# mcu.net
KiCad netlist of a schematic drawn in EAGLE
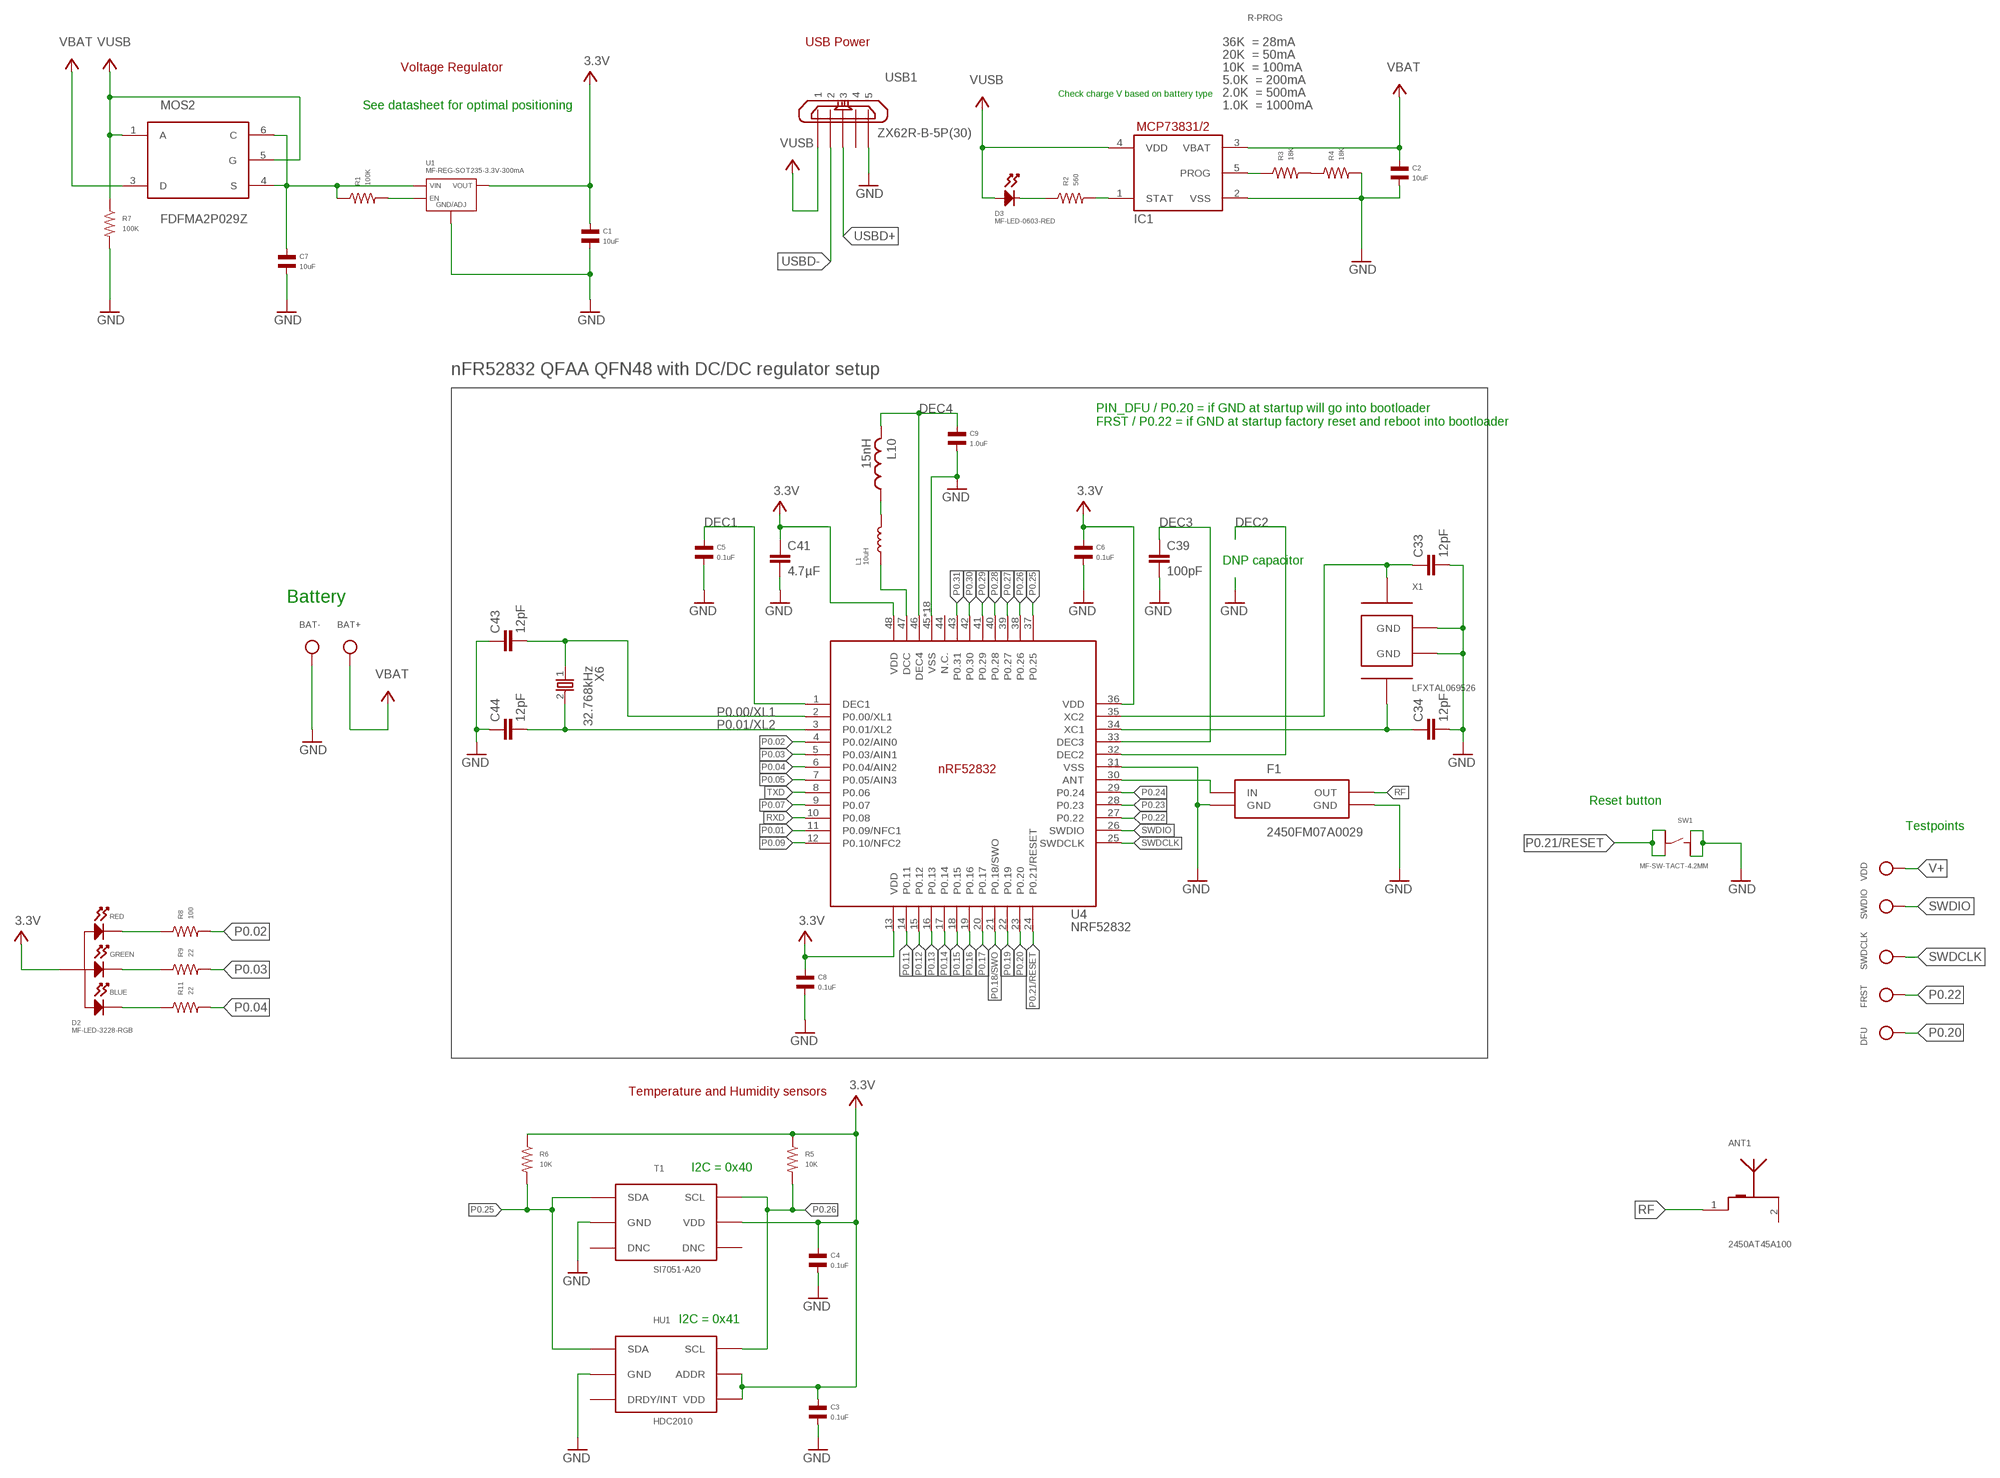
[diagram p0: schematic, sheet 1]

(export (version "E")
  (design (tool "Eeschema 10.0.6"))
  (components
    (comp (ref "ANT1")
      (value "2450AT45A100")
      (footprint "eagle-import:2450AT45A100")
      (fields (field (name "MPN") "2450AT45A100E"))
      (libsource (lib "eagle-import") (part "2450AT45A100"))
    )
    (comp (ref "BAT+")
      (value "TESTPOINTROUND2MM")
      (footprint "eagle-import:TESTPOINT_ROUND_2MM")
      (libsource (lib "eagle-import") (part "TESTPOINTROUND2MM"))
    )
    (comp (ref "BAT-")
      (value "TESTPOINTROUND2MM")
      (footprint "eagle-import:TESTPOINT_ROUND_2MM")
      (libsource (lib "eagle-import") (part "TESTPOINTROUND2MM"))
    )
    (comp (ref "C1")
      (value "10uF")
      (footprint "eagle-import:C0603")
      (fields (field (name "HOUSEPART") "YES") (field (name "MPN") "JMK107ABJ106KA-T"))
      (libsource (lib "eagle-import") (part "CAPACITOR_NP_0603"))
    )
    (comp (ref "C2")
      (value "10uF")
      (footprint "eagle-import:C0603")
      (fields (field (name "HOUSEPART") "YES") (field (name "MPN") "JMK107ABJ106KA-T"))
      (libsource (lib "eagle-import") (part "CAPACITOR_NP_0603"))
    )
    (comp (ref "C3")
      (value "0.1uF")
      (footprint "eagle-import:C0402")
      (fields (field (name "HOUSEPART") "YES") (field (name "MPN") "MF-CAP-0402-0.1uF"))
      (libsource (lib "eagle-import") (part "CAPACITOR_NP_0402"))
    )
    (comp (ref "C4")
      (value "0.1uF")
      (footprint "eagle-import:C0402")
      (fields (field (name "HOUSEPART") "YES") (field (name "MPN") "MF-CAP-0402-0.1uF"))
      (libsource (lib "eagle-import") (part "CAPACITOR_NP_0402"))
    )
    (comp (ref "C5")
      (value "0.1uF")
      (footprint "eagle-import:C0402")
      (fields (field (name "HOUSEPART") "YES") (field (name "MPN") "MF-CAP-0402-0.1uF"))
      (libsource (lib "eagle-import") (part "CAPACITOR_NP_0402"))
    )
    (comp (ref "C6")
      (value "0.1uF")
      (footprint "eagle-import:C0402")
      (fields (field (name "HOUSEPART") "YES") (field (name "MPN") "MF-CAP-0402-0.1uF"))
      (libsource (lib "eagle-import") (part "CAPACITOR_NP_0402"))
    )
    (comp (ref "C7")
      (value "10uF")
      (footprint "eagle-import:C0603")
      (fields (field (name "HOUSEPART") "YES") (field (name "MPN") "JMK107ABJ106KA-T"))
      (libsource (lib "eagle-import") (part "CAPACITOR_NP_0603"))
    )
    (comp (ref "C8")
      (value "0.1uF")
      (footprint "eagle-import:C0402")
      (fields (field (name "HOUSEPART") "YES") (field (name "MPN") "MF-CAP-0402-0.1uF"))
      (libsource (lib "eagle-import") (part "CAPACITOR_NP_0402"))
    )
    (comp (ref "C9")
      (value "1.0uF")
      (footprint "eagle-import:C0603")
      (fields (field (name "HOUSEPART") "YES") (field (name "MPN") "MF-CAP-0603-1uF"))
      (libsource (lib "eagle-import") (part "CAPACITOR_NP_0603"))
    )
    (comp (ref "C33")
      (value "12pF")
      (footprint "eagle-import:RESC0402_N")
      (fields (field (name "MPN") "C0402C120J5GACTU"))
      (libsource (lib "eagle-import") (part "CAPACITOR_0402_N"))
    )
    (comp (ref "C34")
      (value "12pF")
      (footprint "eagle-import:RESC0402_N")
      (fields (field (name "MPN") "C0402C120J5GACTU"))
      (libsource (lib "eagle-import") (part "CAPACITOR_0402_N"))
    )
    (comp (ref "C39")
      (value "100pF")
      (footprint "eagle-import:RESC0402_N")
      (fields (field (name "MPN") "GRM1555C1H101GA01D"))
      (libsource (lib "eagle-import") (part "CAPACITOR_0402_N"))
    )
    (comp (ref "C41")
      (value "4.7µF")
      (footprint "eagle-import:RESC0603_N")
      (fields (field (name "MPN") "06036D475KAT2A"))
      (libsource (lib "eagle-import") (part "CAPACITOR_0603_N"))
    )
    (comp (ref "C43")
      (value "12pF")
      (footprint "eagle-import:RESC0402_N")
      (fields (field (name "MPN") "C0402C120J5GACTU"))
      (libsource (lib "eagle-import") (part "CAPACITOR_0402_N"))
    )
    (comp (ref "C44")
      (value "12pF")
      (footprint "eagle-import:RESC0402_N")
      (fields (field (name "MPN") "C0402C120J5GACTU"))
      (libsource (lib "eagle-import") (part "CAPACITOR_0402_N"))
    )
    (comp (ref "D2")
      (value "MF-LED-3228-RGB")
      (footprint "eagle-import:PLCC4")
      (fields (field (name "HOUSEPART") "YES"))
      (libsource (lib "eagle-import") (part "LED_RGB_CA_PLCC4"))
    )
    (comp (ref "D3")
      (value "MF-LED-0603-RED")
      (footprint "eagle-import:LED0603")
      (fields (field (name "HOUSEPART") "YES"))
      (libsource (lib "eagle-import") (part "LED_SINGLE-0603-RED"))
    )
    (comp (ref "DFU")
      (value "TESTPOINTROUND2MM")
      (footprint "eagle-import:TESTPOINT_ROUND_2MM")
      (libsource (lib "eagle-import") (part "TESTPOINTROUND2MM"))
    )
    (comp (ref "F1")
      (value "2450FM07A0029")
      (footprint "eagle-import:0402_RF")
      (fields (field (name "MPN") "2450FM07A0029T"))
      (libsource (lib "eagle-import") (part "2450FM07A0029"))
    )
    (comp (ref "FRST")
      (value "TESTPOINTROUND2MM")
      (footprint "eagle-import:TESTPOINT_ROUND_2MM")
      (libsource (lib "eagle-import") (part "TESTPOINTROUND2MM"))
    )
    (comp (ref "HU1")
      (value "HDC2010")
      (footprint "eagle-import:DSBGA-6")
      (fields (field (name "MPN") "HDC2010YPAR"))
      (libsource (lib "eagle-import") (part "HDC2010"))
    )
    (comp (ref "IC1")
      (value "MCP73831/OT")
      (footprint "eagle-import:SOT23-5L")
      (fields (field (name "MPN") "MCP73831T-2ACI/OT"))
      (libsource (lib "eagle-import") (part "MCP73831/OT"))
    )
    (comp (ref "L1")
      (value "10uH")
      (footprint "eagle-import:L1210")
      (fields (field (name "HOUSEPART") "YES") (field (name "MPN") "MF-IND-1210-10uH"))
      (libsource (lib "eagle-import") (part "INDUCTOR_1210"))
    )
    (comp (ref "L10")
      (value "15nH")
      (footprint "eagle-import:RESC0402_N")
      (fields (field (name "MPN") "L-07C15NJV6T"))
      (libsource (lib "eagle-import") (part "INDUCTOR_0402_N"))
    )
    (comp (ref "MOS2")
      (value "FDFMA2P029Z")
      (footprint "eagle-import:MICROFET_2X2")
      (libsource (lib "eagle-import") (part "FDFMA2P029Z"))
    )
    (comp (ref "R1")
      (value "100K")
      (footprint "eagle-import:R0402")
      (fields (field (name "HOUSEPART") "YES") (field (name "MPN") "MF-RES-0402-100K"))
      (libsource (lib "eagle-import") (part "RESISTOR_0402"))
    )
    (comp (ref "R2")
      (value "560")
      (footprint "eagle-import:R0402")
      (fields (field (name "HOUSEPART") "YES") (field (name "MPN") "MF-RES-0402-560"))
      (libsource (lib "eagle-import") (part "RESISTOR_0402"))
    )
    (comp (ref "R3")
      (value "18K")
      (footprint "eagle-import:R0402")
      (fields (field (name "HOUSEPART") "YES") (field (name "MPN") "MF-RES-0402-18K"))
      (libsource (lib "eagle-import") (part "RESISTOR_0402"))
    )
    (comp (ref "R4")
      (value "18K")
      (footprint "eagle-import:R0402")
      (fields (field (name "HOUSEPART") "YES") (field (name "MPN") "MF-RES-0402-18K"))
      (libsource (lib "eagle-import") (part "RESISTOR_0402"))
    )
    (comp (ref "R5")
      (value "10K")
      (footprint "eagle-import:R0402")
      (fields (field (name "HOUSEPART") "YES") (field (name "MPN") "MF-RES-0402-10K"))
      (libsource (lib "eagle-import") (part "RESISTOR_0402"))
    )
    (comp (ref "R6")
      (value "10K")
      (footprint "eagle-import:R0402")
      (fields (field (name "HOUSEPART") "YES") (field (name "MPN") "MF-RES-0402-10K"))
      (libsource (lib "eagle-import") (part "RESISTOR_0402"))
    )
    (comp (ref "R7")
      (value "100K")
      (footprint "eagle-import:R0402")
      (fields (field (name "HOUSEPART") "YES") (field (name "MPN") "MF-RES-0402-100K"))
      (libsource (lib "eagle-import") (part "RESISTOR_0402"))
    )
    (comp (ref "R8")
      (value "100")
      (footprint "eagle-import:R0402")
      (fields (field (name "HOUSEPART") "YES") (field (name "MPN") "MF-RES-0402-100"))
      (libsource (lib "eagle-import") (part "RESISTOR_0402"))
    )
    (comp (ref "R9")
      (value "22")
      (footprint "eagle-import:R0402")
      (fields (field (name "HOUSEPART") "YES") (field (name "MPN") "MF-RES-0402-22"))
      (libsource (lib "eagle-import") (part "RESISTOR_0402"))
    )
    (comp (ref "R11")
      (value "22")
      (footprint "eagle-import:R0402")
      (fields (field (name "HOUSEPART") "YES") (field (name "MPN") "MF-RES-0402-22"))
      (libsource (lib "eagle-import") (part "RESISTOR_0402"))
    )
    (comp (ref "SW1")
      (value "MF-SW-TACT-4.2MM")
      (footprint "eagle-import:TACT4.2MM")
      (fields (field (name "HOUSEPART") "YES"))
      (libsource (lib "eagle-import") (part "TACT_4.2MM"))
    )
    (comp (ref "SWDCLK")
      (value "TESTPOINTROUND2MM")
      (footprint "eagle-import:TESTPOINT_ROUND_2MM")
      (libsource (lib "eagle-import") (part "TESTPOINTROUND2MM"))
    )
    (comp (ref "SWDIO")
      (value "TESTPOINTROUND2MM")
      (footprint "eagle-import:TESTPOINT_ROUND_2MM")
      (libsource (lib "eagle-import") (part "TESTPOINTROUND2MM"))
    )
    (comp (ref "T1")
      (value "SI7051-A20")
      (footprint "eagle-import:DFN-6")
      (fields (field (name "MPN") "SI7051-A20-IM"))
      (libsource (lib "eagle-import") (part "SI7051-A20"))
    )
    (comp (ref "U1")
      (value "MF-REG-SOT235-3.3V-300mA")
      (footprint "eagle-import:SOT-23-5")
      (fields (field (name "HOUSEPART") "YES"))
      (libsource (lib "eagle-import") (part "TLV70233PDBVR"))
    )
    (comp (ref "U4")
      (value "NRF52832")
      (footprint "eagle-import:QFN40P600X600X90-48_N")
      (fields (field (name "MPN") "NRF52832-QFAA-R7"))
      (libsource (lib "eagle-import") (part "NRF52832"))
    )
    (comp (ref "USB1")
      (value "ZX62R-B-5P(30)")
      (footprint "eagle-import:ZX62R-B-5P(30)")
      (libsource (lib "eagle-import") (part "ZX62R-B-5P(30)"))
    )
    (comp (ref "VDD")
      (value "TESTPOINTROUND2MM")
      (footprint "eagle-import:TESTPOINT_ROUND_2MM")
      (libsource (lib "eagle-import") (part "TESTPOINTROUND2MM"))
    )
    (comp (ref "X1")
      (value "LFXTAL069526")
      (footprint "eagle-import:1612")
      (fields (field (name "MPN") "LFXTAL069526CUTT"))
      (libsource (lib "eagle-import") (part "LFXTAL069526"))
    )
    (comp (ref "X6")
      (value "32.768kHz")
      (footprint "eagle-import:XTAL_3215_N")
      (fields (field (name "MPN") "LFXTAL009706REEL"))
      (libsource (lib "eagle-import") (part "XTAL_32KHZ"))
    )
  )
  (nets
    (net (code "1") (name "/DEC1") (class "Default")
      (node (ref "C5") (pin "P$1") (pinfunction "P$1_P$1") (pintype "passive"))
      (node (ref "U4") (pin "1") (pinfunction "DEC1_1") (pintype "power_in"))
    )
    (net (code "2") (name "/DEC2") (class "Default")
      (node (ref "U4") (pin "32") (pinfunction "DEC2_32") (pintype "bidirectional"))
    )
    (net (code "3") (name "/DEC3") (class "Default")
      (node (ref "C39") (pin "1") (pinfunction "1_1") (pintype "passive"))
      (node (ref "U4") (pin "33") (pinfunction "DEC3_33") (pintype "bidirectional"))
    )
    (net (code "4") (name "/DEC4") (class "Default")
      (node (ref "C9") (pin "P$1") (pinfunction "P$1_P$1") (pintype "passive"))
      (node (ref "L10") (pin "2") (pinfunction "2_2") (pintype "passive"))
      (node (ref "U4") (pin "46") (pinfunction "DEC4_46") (pintype "power_in"))
    )
    (net (code "5") (name "/P0.00{slash}XL1") (class "Default")
      (node (ref "C43") (pin "2") (pinfunction "2_2") (pintype "passive"))
      (node (ref "U4") (pin "2") (pinfunction "P0.00/XL1_2") (pintype "bidirectional"))
      (node (ref "X6") (pin "1") (pinfunction "1_1") (pintype "passive"))
    )
    (net (code "6") (name "/P0.01{slash}XL2") (class "Default")
      (node (ref "C44") (pin "2") (pinfunction "2_2") (pintype "passive"))
      (node (ref "U4") (pin "3") (pinfunction "P0.01/XL2_3") (pintype "bidirectional"))
      (node (ref "X6") (pin "2") (pinfunction "2_2") (pintype "passive"))
    )
    (net (code "7") (name "GND") (class "Default")
      (node (ref "BAT-") (pin "P$1") (pinfunction "P$1_P$1") (pintype "bidirectional"))
      (node (ref "C1") (pin "P$2") (pinfunction "P$2_P$2") (pintype "passive"))
      (node (ref "C2") (pin "P$2") (pinfunction "P$2_P$2") (pintype "passive"))
      (node (ref "C3") (pin "P$2") (pinfunction "P$2_P$2") (pintype "passive"))
      (node (ref "C33") (pin "2") (pinfunction "2_2") (pintype "passive"))
      (node (ref "C34") (pin "2") (pinfunction "2_2") (pintype "passive"))
      (node (ref "C39") (pin "2") (pinfunction "2_2") (pintype "passive"))
      (node (ref "C4") (pin "P$2") (pinfunction "P$2_P$2") (pintype "passive"))
      (node (ref "C41") (pin "2") (pinfunction "2_2") (pintype "passive"))
      (node (ref "C43") (pin "1") (pinfunction "1_1") (pintype "passive"))
      (node (ref "C44") (pin "1") (pinfunction "1_1") (pintype "passive"))
      (node (ref "C5") (pin "P$2") (pinfunction "P$2_P$2") (pintype "passive"))
      (node (ref "C6") (pin "P$2") (pinfunction "P$2_P$2") (pintype "passive"))
      (node (ref "C7") (pin "P$2") (pinfunction "P$2_P$2") (pintype "passive"))
      (node (ref "C8") (pin "P$2") (pinfunction "P$2_P$2") (pintype "passive"))
      (node (ref "C9") (pin "P$2") (pinfunction "P$2_P$2") (pintype "passive"))
      (node (ref "F1") (pin "GND@2") (pinfunction "GND_GND@2") (pintype "power_in"))
      (node (ref "F1") (pin "GND@4") (pinfunction "GND_GND@4") (pintype "power_in"))
      (node (ref "HU1") (pin "C1") (pinfunction "GND_C1") (pintype "power_in"))
      (node (ref "IC1") (pin "2") (pinfunction "VSS_2") (pintype "power_in"))
      (node (ref "R4") (pin "P$2") (pinfunction "P$2_P$2") (pintype "passive"))
      (node (ref "R7") (pin "P$2") (pinfunction "P$2_P$2") (pintype "passive"))
      (node (ref "SW1") (pin "P$1") (pinfunction "P$1_P$1") (pintype "bidirectional"))
      (node (ref "SW1") (pin "P$2") (pinfunction "P$2_P$2") (pintype "bidirectional"))
      (node (ref "T1") (pin "2") (pinfunction "GND_2") (pintype "power_in"))
      (node (ref "U1") (pin "P$2") (pinfunction "GND/ADJ_P$2") (pintype "bidirectional"))
      (node (ref "U4") (pin "31") (pinfunction "VSS_31") (pintype "bidirectional"))
      (node (ref "U4") (pin "45") (pinfunction "VSS_45") (pintype "power_in"))
      (node (ref "U4") (pin "PAD") (pinfunction "VSS_PAD") (pintype "power_in"))
      (node (ref "U4") (pin "PAD@VIA01") (pinfunction "VSS_PAD@VIA01") (pintype "power_in"))
      (node (ref "U4") (pin "PAD@VIA02") (pinfunction "VSS_PAD@VIA02") (pintype "power_in"))
      (node (ref "U4") (pin "PAD@VIA03") (pinfunction "VSS_PAD@VIA03") (pintype "power_in"))
      (node (ref "U4") (pin "PAD@VIA04") (pinfunction "VSS_PAD@VIA04") (pintype "power_in"))
      (node (ref "U4") (pin "PAD@VIA05") (pinfunction "VSS_PAD@VIA05") (pintype "power_in"))
      (node (ref "U4") (pin "PAD@VIA06") (pinfunction "VSS_PAD@VIA06") (pintype "power_in"))
      (node (ref "U4") (pin "PAD@VIA07") (pinfunction "VSS_PAD@VIA07") (pintype "power_in"))
      (node (ref "U4") (pin "PAD@VIA08") (pinfunction "VSS_PAD@VIA08") (pintype "power_in"))
      (node (ref "U4") (pin "PAD@VIA09") (pinfunction "VSS_PAD@VIA09") (pintype "power_in"))
      (node (ref "U4") (pin "PAD@VIA10") (pinfunction "VSS_PAD@VIA10") (pintype "power_in"))
      (node (ref "U4") (pin "PAD@VIA11") (pinfunction "VSS_PAD@VIA11") (pintype "power_in"))
      (node (ref "U4") (pin "PAD@VIA12") (pinfunction "VSS_PAD@VIA12") (pintype "power_in"))
      (node (ref "U4") (pin "PAD@VIA13") (pinfunction "VSS_PAD@VIA13") (pintype "power_in"))
      (node (ref "U4") (pin "PAD@VIA14") (pinfunction "VSS_PAD@VIA14") (pintype "power_in"))
      (node (ref "U4") (pin "PAD@VIA15") (pinfunction "VSS_PAD@VIA15") (pintype "power_in"))
      (node (ref "U4") (pin "PAD@VIA16") (pinfunction "VSS_PAD@VIA16") (pintype "power_in"))
      (node (ref "USB1") (pin "5") (pinfunction "5_5") (pintype "passive"))
      (node (ref "X1") (pin "2") (pinfunction "GND_2") (pintype "power_in"))
      (node (ref "X1") (pin "4") (pinfunction "GND_4") (pintype "power_in"))
    )
    (net (code "8") (name "Net-(D2-CATHODE_BLUE)") (class "Default")
      (node (ref "D2") (pin "P$4") (pinfunction "CATHODE_BLUE_P$4") (pintype "power_in"))
      (node (ref "R11") (pin "P$1") (pinfunction "P$1_P$1") (pintype "passive"))
    )
    (net (code "9") (name "Net-(D2-CATHODE_GREEN)") (class "Default")
      (node (ref "D2") (pin "P$3") (pinfunction "CATHODE_GREEN_P$3") (pintype "power_in"))
      (node (ref "R9") (pin "P$1") (pinfunction "P$1_P$1") (pintype "passive"))
    )
    (net (code "10") (name "Net-(D2-CATHODE_RED)") (class "Default")
      (node (ref "D2") (pin "P$2") (pinfunction "CATHODE_RED_P$2") (pintype "power_in"))
      (node (ref "R8") (pin "P$1") (pinfunction "P$1_P$1") (pintype "passive"))
    )
    (net (code "11") (name "Net-(D3-PadCATHODE)") (class "Default")
      (node (ref "D3") (pin "CATHODE") (pinfunction "CATHODE_CATHODE") (pintype "power_in"))
      (node (ref "R2") (pin "P$1") (pinfunction "P$1_P$1") (pintype "passive"))
    )
    (net (code "12") (name "Net-(F1-IN)") (class "Default")
      (node (ref "F1") (pin "1") (pinfunction "IN_1") (pintype "input"))
      (node (ref "U4") (pin "30") (pinfunction "ANT_30") (pintype "bidirectional"))
    )
    (net (code "13") (name "Net-(IC1-PROG)") (class "Default")
      (node (ref "IC1") (pin "5") (pinfunction "PROG_5") (pintype "input"))
      (node (ref "R3") (pin "P$1") (pinfunction "P$1_P$1") (pintype "passive"))
    )
    (net (code "14") (name "Net-(IC1-STAT)") (class "Default")
      (node (ref "IC1") (pin "1") (pinfunction "STAT_1") (pintype "output"))
      (node (ref "R2") (pin "P$2") (pinfunction "P$2_P$2") (pintype "passive"))
    )
    (net (code "15") (name "Net-(L1-PadP$2)") (class "Default")
      (node (ref "L1") (pin "P$2") (pinfunction "P$2_P$2") (pintype "passive"))
      (node (ref "L10") (pin "1") (pinfunction "1_1") (pintype "passive"))
    )
    (net (code "16") (name "Net-(MOS2-C)") (class "Default")
      (node (ref "C7") (pin "P$1") (pinfunction "P$1_P$1") (pintype "passive"))
      (node (ref "MOS2") (pin "4") (pinfunction "S_4") (pintype "bidirectional"))
      (node (ref "MOS2") (pin "6") (pinfunction "C_6") (pintype "bidirectional"))
      (node (ref "R1") (pin "P$1") (pinfunction "P$1_P$1") (pintype "passive"))
      (node (ref "U1") (pin "P$1") (pinfunction "VIN_P$1") (pintype "bidirectional"))
    )
    (net (code "17") (name "Net-(R3-PadP$2)") (class "Default")
      (node (ref "R3") (pin "P$2") (pinfunction "P$2_P$2") (pintype "passive"))
      (node (ref "R4") (pin "P$1") (pinfunction "P$1_P$1") (pintype "passive"))
    )
    (net (code "18") (name "Net-(U1-EN)") (class "Default")
      (node (ref "R1") (pin "P$2") (pinfunction "P$2_P$2") (pintype "passive"))
      (node (ref "U1") (pin "P$3") (pinfunction "EN_P$3") (pintype "bidirectional"))
    )
    (net (code "19") (name "Net-(U4-DCC)") (class "Default")
      (node (ref "L1") (pin "P$1") (pinfunction "P$1_P$1") (pintype "passive"))
      (node (ref "U4") (pin "47") (pinfunction "DCC_47") (pintype "output"))
    )
    (net (code "20") (name "Net-(U4-XC1)") (class "Default")
      (node (ref "C34") (pin "1") (pinfunction "1_1") (pintype "passive"))
      (node (ref "U4") (pin "34") (pinfunction "XC1_34") (pintype "input"))
      (node (ref "X1") (pin "1") (pinfunction "1_1") (pintype "bidirectional"))
    )
    (net (code "21") (name "Net-(U4-XC2)") (class "Default")
      (node (ref "C33") (pin "1") (pinfunction "1_1") (pintype "passive"))
      (node (ref "U4") (pin "35") (pinfunction "XC2_35") (pintype "output"))
      (node (ref "X1") (pin "3") (pinfunction "2_3") (pintype "bidirectional"))
    )
    (net (code "22") (name "P0.01") (class "Default")
      (node (ref "U4") (pin "11") (pinfunction "P0.09/NFC1_11") (pintype "bidirectional"))
    )
    (net (code "23") (name "P0.02") (class "Default")
      (node (ref "R8") (pin "P$2") (pinfunction "P$2_P$2") (pintype "passive"))
      (node (ref "U4") (pin "4") (pinfunction "P0.02/AIN0_4") (pintype "bidirectional"))
    )
    (net (code "24") (name "P0.03") (class "Default")
      (node (ref "R9") (pin "P$2") (pinfunction "P$2_P$2") (pintype "passive"))
      (node (ref "U4") (pin "5") (pinfunction "P0.03/AIN1_5") (pintype "bidirectional"))
    )
    (net (code "25") (name "P0.04") (class "Default")
      (node (ref "R11") (pin "P$2") (pinfunction "P$2_P$2") (pintype "passive"))
      (node (ref "U4") (pin "6") (pinfunction "P0.04/AIN2_6") (pintype "bidirectional"))
    )
    (net (code "26") (name "P0.05") (class "Default")
      (node (ref "U4") (pin "7") (pinfunction "P0.05/AIN3_7") (pintype "bidirectional"))
    )
    (net (code "27") (name "P0.07") (class "Default")
      (node (ref "U4") (pin "9") (pinfunction "P0.07_9") (pintype "bidirectional"))
    )
    (net (code "28") (name "P0.09") (class "Default")
      (node (ref "U4") (pin "12") (pinfunction "P0.10/NFC2_12") (pintype "bidirectional"))
    )
    (net (code "29") (name "P0.11") (class "Default")
      (node (ref "U4") (pin "14") (pinfunction "P0.11_14") (pintype "bidirectional"))
    )
    (net (code "30") (name "P0.12") (class "Default")
      (node (ref "U4") (pin "15") (pinfunction "P0.12_15") (pintype "bidirectional"))
    )
    (net (code "31") (name "P0.13") (class "Default")
      (node (ref "U4") (pin "16") (pinfunction "P0.13_16") (pintype "bidirectional"))
    )
    (net (code "32") (name "P0.14") (class "Default")
      (node (ref "U4") (pin "17") (pinfunction "P0.14_17") (pintype "bidirectional"))
    )
    (net (code "33") (name "P0.15") (class "Default")
      (node (ref "U4") (pin "18") (pinfunction "P0.15_18") (pintype "bidirectional"))
    )
    (net (code "34") (name "P0.16") (class "Default")
      (node (ref "U4") (pin "19") (pinfunction "P0.16_19") (pintype "bidirectional"))
    )
    (net (code "35") (name "P0.17") (class "Default")
      (node (ref "U4") (pin "20") (pinfunction "P0.17_20") (pintype "bidirectional"))
    )
    (net (code "36") (name "P0.18{slash}SWO") (class "Default")
      (node (ref "U4") (pin "21") (pinfunction "P0.18/SWO_21") (pintype "bidirectional"))
    )
    (net (code "37") (name "P0.19") (class "Default")
      (node (ref "U4") (pin "22") (pinfunction "P0.19_22") (pintype "bidirectional"))
    )
    (net (code "38") (name "P0.20") (class "Default")
      (node (ref "DFU") (pin "P$1") (pinfunction "P$1_P$1") (pintype "bidirectional"))
      (node (ref "U4") (pin "23") (pinfunction "P0.20_23") (pintype "bidirectional"))
    )
    (net (code "39") (name "P0.21{slash}RESET") (class "Default")
      (node (ref "SW1") (pin "P$3") (pinfunction "P$3_P$3") (pintype "bidirectional"))
      (node (ref "SW1") (pin "P$4") (pinfunction "P$4_P$4") (pintype "bidirectional"))
      (node (ref "U4") (pin "24") (pinfunction "P0.21/RESET_24") (pintype "bidirectional"))
    )
    (net (code "40") (name "P0.22") (class "Default")
      (node (ref "FRST") (pin "P$1") (pinfunction "P$1_P$1") (pintype "bidirectional"))
      (node (ref "U4") (pin "27") (pinfunction "P0.22_27") (pintype "bidirectional"))
    )
    (net (code "41") (name "P0.23") (class "Default")
      (node (ref "U4") (pin "28") (pinfunction "P0.23_28") (pintype "bidirectional"))
    )
    (net (code "42") (name "P0.24") (class "Default")
      (node (ref "U4") (pin "29") (pinfunction "P0.24_29") (pintype "bidirectional"))
    )
    (net (code "43") (name "P0.25") (class "Default")
      (node (ref "HU1") (pin "A2") (pinfunction "SDA_A2") (pintype "bidirectional"))
      (node (ref "R6") (pin "P$2") (pinfunction "P$2_P$2") (pintype "passive"))
      (node (ref "T1") (pin "1") (pinfunction "SDA_1") (pintype "bidirectional"))
      (node (ref "U4") (pin "37") (pinfunction "P0.25_37") (pintype "bidirectional"))
    )
    (net (code "44") (name "P0.26") (class "Default")
      (node (ref "HU1") (pin "B2") (pinfunction "SCL_B2") (pintype "input"))
      (node (ref "R5") (pin "P$2") (pinfunction "P$2_P$2") (pintype "passive"))
      (node (ref "T1") (pin "6") (pinfunction "SCL_6") (pintype "bidirectional"))
      (node (ref "U4") (pin "38") (pinfunction "P0.26_38") (pintype "bidirectional"))
    )
    (net (code "45") (name "P0.27") (class "Default")
      (node (ref "U4") (pin "39") (pinfunction "P0.27_39") (pintype "bidirectional"))
    )
    (net (code "46") (name "P0.28") (class "Default")
      (node (ref "U4") (pin "40") (pinfunction "P0.28_40") (pintype "bidirectional"))
    )
    (net (code "47") (name "P0.29") (class "Default")
      (node (ref "U4") (pin "41") (pinfunction "P0.29_41") (pintype "bidirectional"))
    )
    (net (code "48") (name "P0.30") (class "Default")
      (node (ref "U4") (pin "42") (pinfunction "P0.30_42") (pintype "bidirectional"))
    )
    (net (code "49") (name "P0.31") (class "Default")
      (node (ref "U4") (pin "43") (pinfunction "P0.31_43") (pintype "bidirectional"))
    )
    (net (code "50") (name "RF") (class "Default")
      (node (ref "ANT1") (pin "1") (pinfunction "1_1") (pintype "bidirectional"))
      (node (ref "F1") (pin "3") (pinfunction "OUT_3") (pintype "output"))
    )
    (net (code "51") (name "RXD") (class "Default")
      (node (ref "U4") (pin "10") (pinfunction "P0.08_10") (pintype "bidirectional"))
    )
    (net (code "52") (name "SWDCLK") (class "Default")
      (node (ref "SWDCLK") (pin "P$1") (pinfunction "P$1_P$1") (pintype "bidirectional"))
      (node (ref "U4") (pin "25") (pinfunction "SWDCLK_25") (pintype "input"))
    )
    (net (code "53") (name "SWDIO") (class "Default")
      (node (ref "SWDIO") (pin "P$1") (pinfunction "P$1_P$1") (pintype "bidirectional"))
      (node (ref "U4") (pin "26") (pinfunction "SWDIO_26") (pintype "bidirectional"))
    )
    (net (code "54") (name "TXD") (class "Default")
      (node (ref "U4") (pin "8") (pinfunction "P0.06_8") (pintype "bidirectional"))
    )
    (net (code "55") (name "USBD+") (class "Default")
      (node (ref "USB1") (pin "3") (pinfunction "3_3") (pintype "passive"))
    )
    (net (code "56") (name "USBD-") (class "Default")
      (node (ref "USB1") (pin "2") (pinfunction "2_2") (pintype "passive"))
    )
    (net (code "57") (name "V+") (class "Default")
      (node (ref "C1") (pin "P$1") (pinfunction "P$1_P$1") (pintype "passive"))
      (node (ref "C3") (pin "P$1") (pinfunction "P$1_P$1") (pintype "passive"))
      (node (ref "C4") (pin "P$1") (pinfunction "P$1_P$1") (pintype "passive"))
      (node (ref "C41") (pin "1") (pinfunction "1_1") (pintype "passive"))
      (node (ref "C6") (pin "P$1") (pinfunction "P$1_P$1") (pintype "passive"))
      (node (ref "C8") (pin "P$1") (pinfunction "P$1_P$1") (pintype "passive"))
      (node (ref "D2") (pin "P$1") (pinfunction "ANODE_P$1") (pintype "power_in"))
      (node (ref "HU1") (pin "A1") (pinfunction "VDD_A1") (pintype "power_in"))
      (node (ref "HU1") (pin "B1") (pinfunction "ADDR_B1") (pintype "input"))
      (node (ref "R5") (pin "P$1") (pinfunction "P$1_P$1") (pintype "passive"))
      (node (ref "R6") (pin "P$1") (pinfunction "P$1_P$1") (pintype "passive"))
      (node (ref "T1") (pin "5") (pinfunction "VDD_5") (pintype "power_in"))
      (node (ref "U1") (pin "P$5") (pinfunction "VOUT_P$5") (pintype "bidirectional"))
      (node (ref "U4") (pin "13") (pinfunction "VDD_13") (pintype "power_in"))
      (node (ref "U4") (pin "36") (pinfunction "VDD_36") (pintype "power_in"))
      (node (ref "U4") (pin "48") (pinfunction "VDD_48") (pintype "power_in"))
      (node (ref "VDD") (pin "P$1") (pinfunction "P$1_P$1") (pintype "bidirectional"))
    )
    (net (code "58") (name "VBAT") (class "Default")
      (node (ref "BAT+") (pin "P$1") (pinfunction "P$1_P$1") (pintype "bidirectional"))
      (node (ref "C2") (pin "P$1") (pinfunction "P$1_P$1") (pintype "passive"))
      (node (ref "IC1") (pin "3") (pinfunction "VBAT_3") (pintype "bidirectional"))
      (node (ref "MOS2") (pin "3") (pinfunction "D_3") (pintype "bidirectional"))
    )
    (net (code "59") (name "VUSB") (class "Default")
      (node (ref "D3") (pin "ANODE") (pinfunction "ANODE_ANODE") (pintype "power_in"))
      (node (ref "IC1") (pin "4") (pinfunction "VDD_4") (pintype "power_in"))
      (node (ref "MOS2") (pin "1") (pinfunction "A_1") (pintype "bidirectional"))
      (node (ref "MOS2") (pin "5") (pinfunction "G_5") (pintype "bidirectional"))
      (node (ref "R7") (pin "P$1") (pinfunction "P$1_P$1") (pintype "passive"))
      (node (ref "USB1") (pin "1") (pinfunction "1_1") (pintype "passive"))
    )
    (net (code "60") (name "unconnected-(ANT1-Pad2)") (class "Default")
      (node (ref "ANT1") (pin "2") (pinfunction "2_2") (pintype "no_connect"))
    )
    (net (code "61") (name "unconnected-(HU1-DRDY{slash}INT-PadC2)") (class "Default")
      (node (ref "HU1") (pin "C2") (pinfunction "DRDY/INT_C2") (pintype "output"))
    )
    (net (code "62") (name "unconnected-(T1-DNC-Pad3)") (class "Default")
      (node (ref "T1") (pin "3") (pinfunction "DNC_3") (pintype "no_connect"))
    )
    (net (code "63") (name "unconnected-(T1-DNC-Pad4)") (class "Default")
      (node (ref "T1") (pin "4") (pinfunction "DNC_4") (pintype "no_connect"))
    )
    (net (code "64") (name "unconnected-(U4-N.C.-Pad44)") (class "Default")
      (node (ref "U4") (pin "44") (pinfunction "N.C._44") (pintype "no_connect"))
    )
    (net (code "65") (name "unconnected-(USB1-Pad4)") (class "Default")
      (node (ref "USB1") (pin "4") (pinfunction "4_4") (pintype "passive"))
    )
  )
)
